# Alimenta_o.net
KiCad netlist of a schematic drawn in Altium Designer
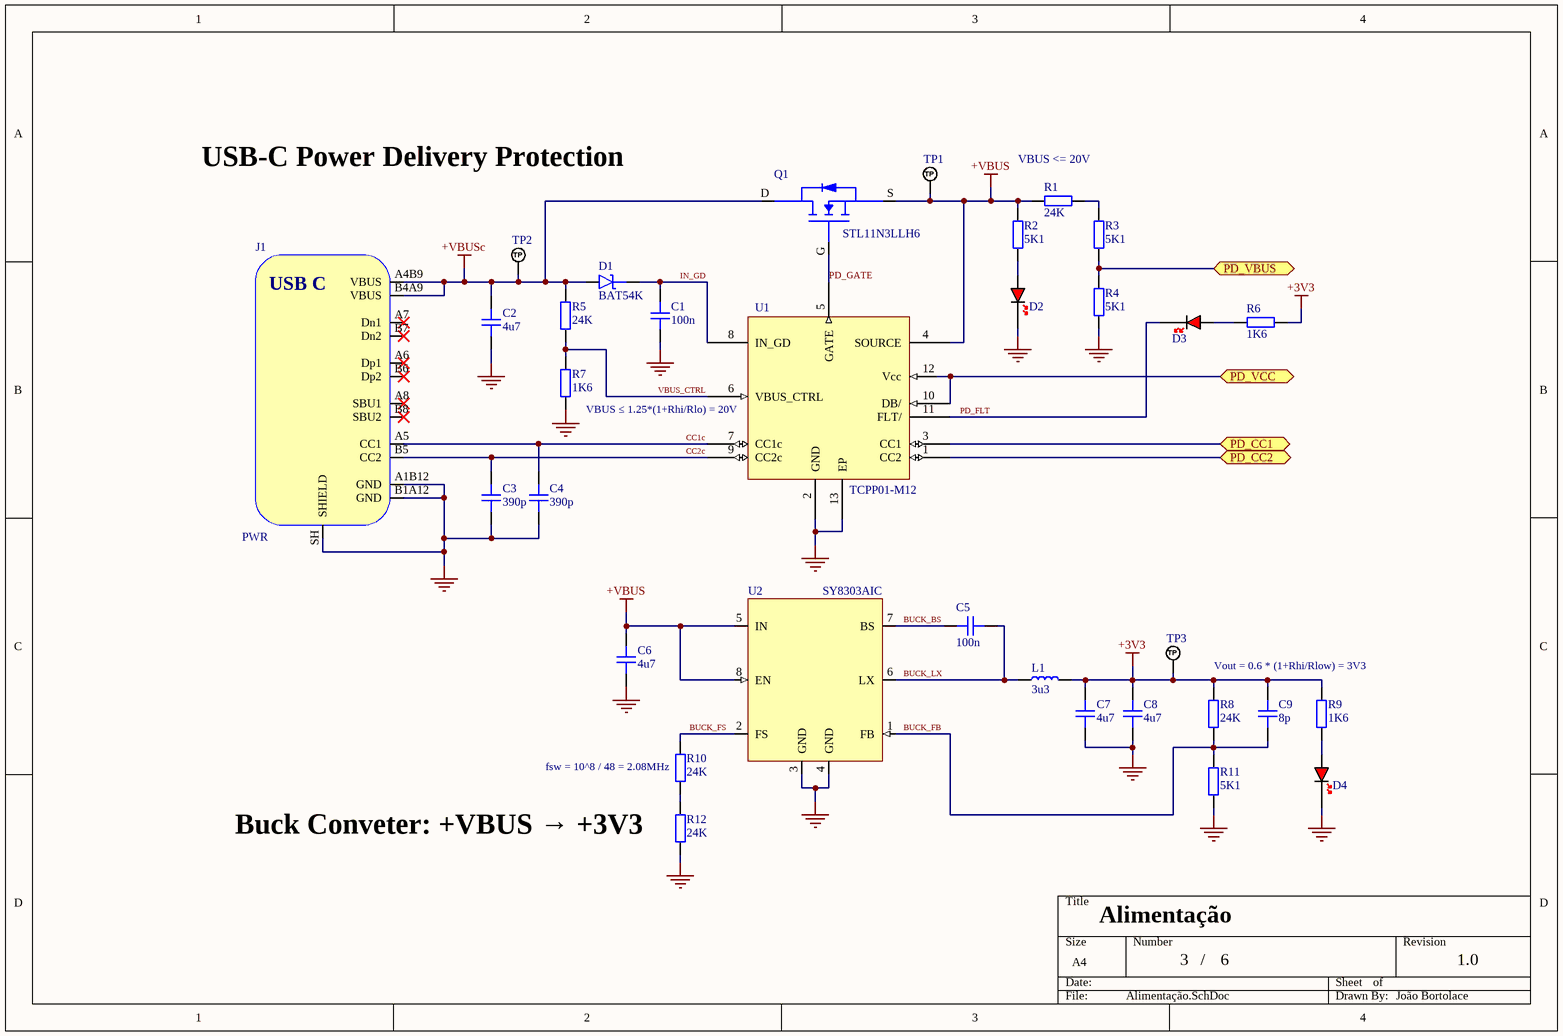
[diagram p0: Alimentação.SchDoc]

(export (version "E")
  (design (tool "Eeschema 10.0.6"))
  (components
    (comp (ref "C1")
      (value "100n")
      (footprint "CAP_0402")
      (description "100nF ±10% 50V Ceramic Capacitor X7R 0402D 0402")
      (fields
        (field (name "MANUFACTURER") "muRata")
        (field (name "MANUFACTURER PART NUMBER") "GRM155R71H104KE14D")
      )
      (libsource (lib "Schematic-Lib-PhilsLab") (part "CAP_0402"))
    )
    (comp (ref "C2")
      (value "4u7")
      (footprint "CAP_0805")
      (description "4.7uF ±10% 50V Ceramic Capacitor X5R 0805")
      (fields
        (field (name "MANUFACTURER") "Samsung Electro-Mechanics")
        (field (name "MANUFACTURER PART NUMBER") "CL21A475KBQNNNE")
      )
      (libsource (lib "Schematic-Lib-PhilsLab") (part "CAP_0805"))
    )
    (comp (ref "C3")
      (value "390p")
      (footprint "CAP_0603")
      (description "390pF ±5% 50V Ceramic Capacitor C0G 0603")
      (fields
        (field (name "MANUFACTURER") "muRata")
        (field (name "MANUFACTURER PART NUMBER") "GRM1885C1H391JA01D")
      )
      (libsource (lib "Schematic-Lib-PhilsLab") (part "CAP_0603"))
    )
    (comp (ref "C4")
      (value "390p")
      (footprint "CAP_0603")
      (description "390pF ±5% 50V Ceramic Capacitor C0G 0603")
      (fields
        (field (name "MANUFACTURER") "muRata")
        (field (name "MANUFACTURER PART NUMBER") "GRM1885C1H391JA01D")
      )
      (libsource (lib "Schematic-Lib-PhilsLab") (part "CAP_0603"))
    )
    (comp (ref "C5")
      (value "100n")
      (footprint "CAP_0402")
      (description "100nF ±10% 50V Ceramic Capacitor X7R 0402D 0402")
      (fields
        (field (name "MANUFACTURER") "muRata")
        (field (name "MANUFACTURER PART NUMBER") "GRM155R71H104KE14D")
      )
      (libsource (lib "Schematic-Lib-PhilsLab") (part "CAP_0402"))
    )
    (comp (ref "C6")
      (value "4u7")
      (footprint "CAP_0805")
      (description "4.7uF ±10% 50V Ceramic Capacitor X5R 0805")
      (fields
        (field (name "MANUFACTURER") "Samsung Electro-Mechanics")
        (field (name "MANUFACTURER PART NUMBER") "CL21A475KBQNNNE")
      )
      (libsource (lib "Schematic-Lib-PhilsLab") (part "CAP_0805"))
    )
    (comp (ref "C7")
      (value "4u7")
      (footprint "CAP_0805")
      (description "4.7uF ±10% 50V Ceramic Capacitor X5R 0805")
      (fields
        (field (name "MANUFACTURER") "Samsung Electro-Mechanics")
        (field (name "MANUFACTURER PART NUMBER") "CL21A475KBQNNNE")
      )
      (libsource (lib "Schematic-Lib-PhilsLab") (part "CAP_0805"))
    )
    (comp (ref "C8")
      (value "4u7")
      (footprint "CAP_0805")
      (description "4.7uF ±10% 50V Ceramic Capacitor X5R 0805")
      (fields
        (field (name "MANUFACTURER") "Samsung Electro-Mechanics")
        (field (name "MANUFACTURER PART NUMBER") "CL21A475KBQNNNE")
      )
      (libsource (lib "Schematic-Lib-PhilsLab") (part "CAP_0805"))
    )
    (comp (ref "C9")
      (value "8p")
      (footprint "CAP_0402")
      (description "8pF ±1% 50V Ceramic Capacitor C0G 0402")
      (fields
        (field (name "MANUFACTURER") "muRata")
        (field (name "MANUFACTURER PART NUMBER") "GCM1555C1H8R0FA16D")
      )
      (libsource (lib "Schematic-Lib-PhilsLab") (part "CAP_0402"))
    )
    (comp (ref "D1")
      (value "BAT54K")
      (footprint "SOD-323")
      (description "Diode Schottky SMD SOD-323")
      (fields
        (field (name "MANUFACTURER") "STMicroelectronics")
        (field (name "MANUFACTURER PART NUMBER") "BAT54KFILM")
      )
      (libsource (lib "Schematic-Lib-PhilsLab") (part "D_SCHOTTKY_SOD_323"))
    )
    (comp (ref "D2")
      (value "+VBUS")
      (footprint "LED_0402_RED")
      (description "LED 0402 RED SMD")
      (libsource (lib "Schematic-Lib-PhilsLab") (part "LED_0402_RED"))
    )
    (comp (ref "D3")
      (value "FLT")
      (footprint "LED_0402_RED")
      (description "LED 0402 RED SMD")
      (libsource (lib "Schematic-Lib-PhilsLab") (part "LED_0402_RED"))
    )
    (comp (ref "D4")
      (value "+3V3")
      (footprint "LED_0402_RED")
      (description "LED 0402 RED SMD")
      (libsource (lib "Schematic-Lib-PhilsLab") (part "LED_0402_RED"))
    )
    (comp (ref "J1")
      (value "PWR")
      (footprint "USB4105-GF-A-060")
      (description "USB-C (USB TYPE-C) Receptacle Connector 16 Position Surface Mount, Right Angle")
      (fields
        (field (name "MANUFACTURER") "DEALON")
        (field (name "MANUFACTURER PART NUMBER") "USB-TYPE-C-018")
      )
      (libsource (lib "Schematic-Lib-PhilsLab") (part "USB4105-GF-A-060"))
    )
    (comp (ref "L1")
      (value "3u3")
      (footprint "SRP3212A")
      (description "Inductor 3u3 3.4A  87mΩ 1210 Fixed Inductors RoHS")
      (fields
        (field (name "MANUFACTURER") "Bourns")
        (field (name "MANUFACTURER PART NUMBER") "SRP3212A-3R3M")
      )
      (libsource (lib "Schematic-Lib-PhilsLab") (part "SRP3212A-*"))
    )
    (comp (ref "Q1")
      (value "STL11N3LLH6")
      (footprint "PowerFLAT 3.3x3.3")
      (description "Mosfet N-channel 30 V, 6 mΩ typ., 11 A")
      (fields (field (name "MANUFACTURER") "STMicroelectronics"))
      (libsource (lib "Schematic-Lib-PhilsLab") (part "STL11N3LLH6"))
    )
    (comp (ref "R1")
      (value "24K")
      (footprint "RES_0402")
      (description "Resistor SMD 0402")
      (libsource (lib "Schematic-Lib-PhilsLab") (part "RES_0402"))
    )
    (comp (ref "R2")
      (value "5K1")
      (footprint "RES_0402")
      (description "Resistor SMD 0402")
      (libsource (lib "Schematic-Lib-PhilsLab") (part "RES_0402"))
    )
    (comp (ref "R3")
      (value "5K1")
      (footprint "RES_0402")
      (description "Resistor SMD 0402")
      (libsource (lib "Schematic-Lib-PhilsLab") (part "RES_0402"))
    )
    (comp (ref "R4")
      (value "5K1")
      (footprint "RES_0402")
      (description "Resistor SMD 0402")
      (libsource (lib "Schematic-Lib-PhilsLab") (part "RES_0402"))
    )
    (comp (ref "R5")
      (value "24K")
      (footprint "RES_0402")
      (description "Resistor SMD 0402")
      (libsource (lib "Schematic-Lib-PhilsLab") (part "RES_0402"))
    )
    (comp (ref "R6")
      (value "1K6")
      (footprint "RES_0402")
      (description "Resistor SMD 0402")
      (libsource (lib "Schematic-Lib-PhilsLab") (part "RES_0402"))
    )
    (comp (ref "R7")
      (value "1K6")
      (footprint "RES_0402")
      (description "Resistor SMD 0402")
      (libsource (lib "Schematic-Lib-PhilsLab") (part "RES_0402"))
    )
    (comp (ref "R8")
      (value "24K")
      (footprint "RES_0402")
      (description "Resistor SMD 0402")
      (libsource (lib "Schematic-Lib-PhilsLab") (part "RES_0402"))
    )
    (comp (ref "R9")
      (value "1K6")
      (footprint "RES_0402")
      (description "Resistor SMD 0402")
      (libsource (lib "Schematic-Lib-PhilsLab") (part "RES_0402"))
    )
    (comp (ref "R10")
      (value "24K")
      (footprint "RES_0402")
      (description "Resistor SMD 0402")
      (libsource (lib "Schematic-Lib-PhilsLab") (part "RES_0402"))
    )
    (comp (ref "R11")
      (value "5K1")
      (footprint "RES_0402")
      (description "Resistor SMD 0402")
      (libsource (lib "Schematic-Lib-PhilsLab") (part "RES_0402"))
    )
    (comp (ref "R12")
      (value "24K")
      (footprint "RES_0402")
      (description "Resistor SMD 0402")
      (libsource (lib "Schematic-Lib-PhilsLab") (part "RES_0402"))
    )
    (comp (ref "TP1")
      (value "TP_NOBOM")
      (footprint "PAD_RND_1MM")
      (description "Test Point Round 1mm (NO BOM)")
      (libsource (lib "Schematic-Lib-PhilsLab") (part "TEST_POINT_RND_1MM"))
    )
    (comp (ref "TP2")
      (value "TP_NOBOM")
      (footprint "PAD_RND_1MM")
      (description "Test Point Round 1mm (NO BOM)")
      (libsource (lib "Schematic-Lib-PhilsLab") (part "TEST_POINT_RND_1MM"))
    )
    (comp (ref "TP3")
      (value "TP_NOBOM")
      (footprint "PAD_RND_1MM")
      (description "Test Point Round 1mm (NO BOM)")
      (libsource (lib "Schematic-Lib-PhilsLab") (part "TEST_POINT_RND_1MM"))
    )
    (comp (ref "U1")
      (value "TCPP01-M12")
      (footprint "QFN-12L")
      (description "USB Type-C™ and power delivery protection for sink application")
      (fields (field (name "MANUFACTURER") "STMicroelectronics"))
      (libsource (lib "Schematic-Lib-PhilsLab") (part "TCPP01-M12"))
    )
    (comp (ref "U2")
      (value "SY8303AIC")
      (footprint "TSOT23-8")
      (description "High Efficiency Fast Response, 3A, 40V Input Synchronous Step Down Regulator")
      (fields (field (name "MANUFACTURER") "Silergy"))
      (libsource (lib "Schematic-Lib-PhilsLab") (part "SY8303AIC"))
    )
  )
  (nets
    (net (code "1") (name "+3V3") (class "Default")
      (node (ref "C7") (pin "2") (pinfunction "2_2") (pintype "passive"))
      (node (ref "C8") (pin "2") (pinfunction "2_2") (pintype "passive"))
      (node (ref "C9") (pin "2") (pinfunction "2_2") (pintype "passive"))
      (node (ref "L1") (pin "2") (pinfunction "2_2") (pintype "passive"))
      (node (ref "R6") (pin "1") (pinfunction "1_1") (pintype "passive"))
      (node (ref "R8") (pin "2") (pinfunction "2_2") (pintype "passive"))
      (node (ref "R9") (pin "2") (pinfunction "2_2") (pintype "passive"))
      (node (ref "TP3") (pin "1") (pinfunction "TP_1") (pintype "passive"))
    )
    (net (code "2") (name "+VBUS") (class "Default")
      (node (ref "C6") (pin "2") (pinfunction "2_2") (pintype "passive"))
      (node (ref "Q1") (pin "S") (pinfunction "S_S") (pintype "passive"))
      (node (ref "R1") (pin "2") (pinfunction "2_2") (pintype "passive"))
      (node (ref "R2") (pin "2") (pinfunction "2_2") (pintype "passive"))
      (node (ref "TP1") (pin "1") (pinfunction "TP_1") (pintype "passive"))
      (node (ref "U1") (pin "4") (pinfunction "SOURCE_4") (pintype "power_in"))
      (node (ref "U2") (pin "5") (pinfunction "IN_5") (pintype "power_in"))
      (node (ref "U2") (pin "8") (pinfunction "EN_8") (pintype "input"))
    )
    (net (code "3") (name "+VBUSc") (class "Default")
      (node (ref "C2") (pin "2") (pinfunction "2_2") (pintype "passive"))
      (node (ref "D1") (pin "A") (pinfunction "A_A") (pintype "passive"))
      (node (ref "J1") (pin "A4B9") (pinfunction "VBUS_A4B9") (pintype "passive"))
      (node (ref "J1") (pin "B4A9") (pinfunction "VBUS_B4A9") (pintype "passive"))
      (node (ref "Q1") (pin "D") (pinfunction "D_D") (pintype "passive"))
      (node (ref "R5") (pin "2") (pinfunction "2_2") (pintype "passive"))
      (node (ref "TP2") (pin "1") (pinfunction "TP_1") (pintype "passive"))
    )
    (net (code "4") (name "/BUCK_BS") (class "Default")
      (node (ref "C5") (pin "1") (pinfunction "1_1") (pintype "passive"))
      (node (ref "U2") (pin "7") (pinfunction "BS_7") (pintype "power_in"))
    )
    (net (code "5") (name "/BUCK_FB") (class "Default")
      (node (ref "C9") (pin "1") (pinfunction "1_1") (pintype "passive"))
      (node (ref "R11") (pin "2") (pinfunction "2_2") (pintype "passive"))
      (node (ref "R8") (pin "1") (pinfunction "1_1") (pintype "passive"))
      (node (ref "U2") (pin "1") (pinfunction "FB_1") (pintype "input"))
    )
    (net (code "6") (name "/BUCK_FS") (class "Default")
      (node (ref "R10") (pin "2") (pinfunction "2_2") (pintype "passive"))
      (node (ref "U2") (pin "2") (pinfunction "FS_2") (pintype "passive"))
    )
    (net (code "7") (name "/BUCK_LX") (class "Default")
      (node (ref "C5") (pin "2") (pinfunction "2_2") (pintype "passive"))
      (node (ref "L1") (pin "1") (pinfunction "1_1") (pintype "passive"))
      (node (ref "U2") (pin "6") (pinfunction "LX_6") (pintype "power_in"))
    )
    (net (code "8") (name "/CC1c") (class "Default")
      (node (ref "C4") (pin "2") (pinfunction "2_2") (pintype "passive"))
      (node (ref "J1") (pin "A5") (pinfunction "CC1_A5") (pintype "passive"))
      (node (ref "U1") (pin "7") (pinfunction "CC1c_7") (pintype "bidirectional"))
    )
    (net (code "9") (name "/CC2c") (class "Default")
      (node (ref "C3") (pin "2") (pinfunction "2_2") (pintype "passive"))
      (node (ref "J1") (pin "B5") (pinfunction "CC2_B5") (pintype "passive"))
      (node (ref "U1") (pin "9") (pinfunction "CC2c_9") (pintype "bidirectional"))
    )
    (net (code "10") (name "/IN_GD") (class "Default")
      (node (ref "C1") (pin "2") (pinfunction "2_2") (pintype "passive"))
      (node (ref "D1") (pin "K") (pinfunction "K_K") (pintype "passive"))
      (node (ref "U1") (pin "8") (pinfunction "IN_GD_8") (pintype "power_in"))
    )
    (net (code "11") (name "/PD_CC1") (class "Default")
      (node (ref "U1") (pin "3") (pinfunction "CC1_3") (pintype "bidirectional"))
    )
    (net (code "12") (name "/PD_CC2") (class "Default")
      (node (ref "U1") (pin "1") (pinfunction "CC2_1") (pintype "bidirectional"))
    )
    (net (code "13") (name "/PD_FLT") (class "Default")
      (node (ref "D3") (pin "K") (pinfunction "K_K") (pintype "passive"))
      (node (ref "U1") (pin "11") (pinfunction "FLT/_11") (pintype "open_collector"))
    )
    (net (code "14") (name "/PD_GATE") (class "Default")
      (node (ref "Q1") (pin "G") (pinfunction "G_G") (pintype "passive"))
      (node (ref "U1") (pin "5") (pinfunction "GATE_5") (pintype "output"))
    )
    (net (code "15") (name "/PD_VBUS") (class "Default")
      (node (ref "R3") (pin "2") (pinfunction "2_2") (pintype "passive"))
      (node (ref "R4") (pin "2") (pinfunction "2_2") (pintype "passive"))
    )
    (net (code "16") (name "/PD_VCC") (class "Default")
      (node (ref "U1") (pin "10") (pinfunction "DB/_10") (pintype "input"))
      (node (ref "U1") (pin "12") (pinfunction "Vcc_12") (pintype "input"))
    )
    (net (code "17") (name "/VBUS_CTRL") (class "Default")
      (node (ref "R5") (pin "1") (pinfunction "1_1") (pintype "passive"))
      (node (ref "R7") (pin "2") (pinfunction "2_2") (pintype "passive"))
      (node (ref "U1") (pin "6") (pinfunction "VBUS_CTRL_6") (pintype "input"))
    )
    (net (code "18") (name "GND") (class "Default")
      (node (ref "C1") (pin "1") (pinfunction "1_1") (pintype "passive"))
      (node (ref "C2") (pin "1") (pinfunction "1_1") (pintype "passive"))
      (node (ref "C3") (pin "1") (pinfunction "1_1") (pintype "passive"))
      (node (ref "C4") (pin "1") (pinfunction "1_1") (pintype "passive"))
      (node (ref "C6") (pin "1") (pinfunction "1_1") (pintype "passive"))
      (node (ref "C7") (pin "1") (pinfunction "1_1") (pintype "passive"))
      (node (ref "C8") (pin "1") (pinfunction "1_1") (pintype "passive"))
      (node (ref "D2") (pin "K") (pinfunction "K_K") (pintype "passive"))
      (node (ref "D4") (pin "K") (pinfunction "K_K") (pintype "passive"))
      (node (ref "J1") (pin "A1B12") (pinfunction "GND_A1B12") (pintype "passive"))
      (node (ref "J1") (pin "B1A12") (pinfunction "GND_B1A12") (pintype "passive"))
      (node (ref "J1") (pin "SH") (pinfunction "SHIELD_SH") (pintype "passive"))
      (node (ref "R11") (pin "1") (pinfunction "1_1") (pintype "passive"))
      (node (ref "R12") (pin "1") (pinfunction "1_1") (pintype "passive"))
      (node (ref "R4") (pin "1") (pinfunction "1_1") (pintype "passive"))
      (node (ref "R7") (pin "1") (pinfunction "1_1") (pintype "passive"))
      (node (ref "U1") (pin "13") (pinfunction "EP_13") (pintype "power_in"))
      (node (ref "U1") (pin "2") (pinfunction "GND_2") (pintype "power_in"))
      (node (ref "U2") (pin "3") (pinfunction "GND_3") (pintype "power_in"))
      (node (ref "U2") (pin "4") (pinfunction "GND_4") (pintype "power_in"))
    )
    (net (code "19") (name "Net-(D2-PadA)") (class "Default")
      (node (ref "D2") (pin "A") (pinfunction "A_A") (pintype "passive"))
      (node (ref "R2") (pin "1") (pinfunction "1_1") (pintype "passive"))
    )
    (net (code "20") (name "Net-(D3-PadA)") (class "Default")
      (node (ref "D3") (pin "A") (pinfunction "A_A") (pintype "passive"))
      (node (ref "R6") (pin "2") (pinfunction "2_2") (pintype "passive"))
    )
    (net (code "21") (name "Net-(D4-PadA)") (class "Default")
      (node (ref "D4") (pin "A") (pinfunction "A_A") (pintype "passive"))
      (node (ref "R9") (pin "1") (pinfunction "1_1") (pintype "passive"))
    )
    (net (code "22") (name "Net-(R1-Pad1)") (class "Default")
      (node (ref "R1") (pin "1") (pinfunction "1_1") (pintype "passive"))
      (node (ref "R3") (pin "1") (pinfunction "1_1") (pintype "passive"))
    )
    (net (code "23") (name "Net-(R10-Pad1)") (class "Default")
      (node (ref "R10") (pin "1") (pinfunction "1_1") (pintype "passive"))
      (node (ref "R12") (pin "2") (pinfunction "2_2") (pintype "passive"))
    )
    (net (code "24") (name "unconnected-(J1-Dn1-PadA7)") (class "Default")
      (node (ref "J1") (pin "A7") (pinfunction "Dn1_A7") (pintype "passive+no_connect"))
    )
    (net (code "25") (name "unconnected-(J1-Dn2-PadB7)") (class "Default")
      (node (ref "J1") (pin "B7") (pinfunction "Dn2_B7") (pintype "passive+no_connect"))
    )
    (net (code "26") (name "unconnected-(J1-Dp1-PadA6)") (class "Default")
      (node (ref "J1") (pin "A6") (pinfunction "Dp1_A6") (pintype "passive+no_connect"))
    )
    (net (code "27") (name "unconnected-(J1-Dp2-PadB6)") (class "Default")
      (node (ref "J1") (pin "B6") (pinfunction "Dp2_B6") (pintype "passive+no_connect"))
    )
    (net (code "28") (name "unconnected-(J1-SBU1-PadA8)") (class "Default")
      (node (ref "J1") (pin "A8") (pinfunction "SBU1_A8") (pintype "passive+no_connect"))
    )
    (net (code "29") (name "unconnected-(J1-SBU2-PadB8)") (class "Default")
      (node (ref "J1") (pin "B8") (pinfunction "SBU2_B8") (pintype "passive+no_connect"))
    )
  )
)
